# J1.net
KiCad netlist of a schematic drawn in Altium Designer
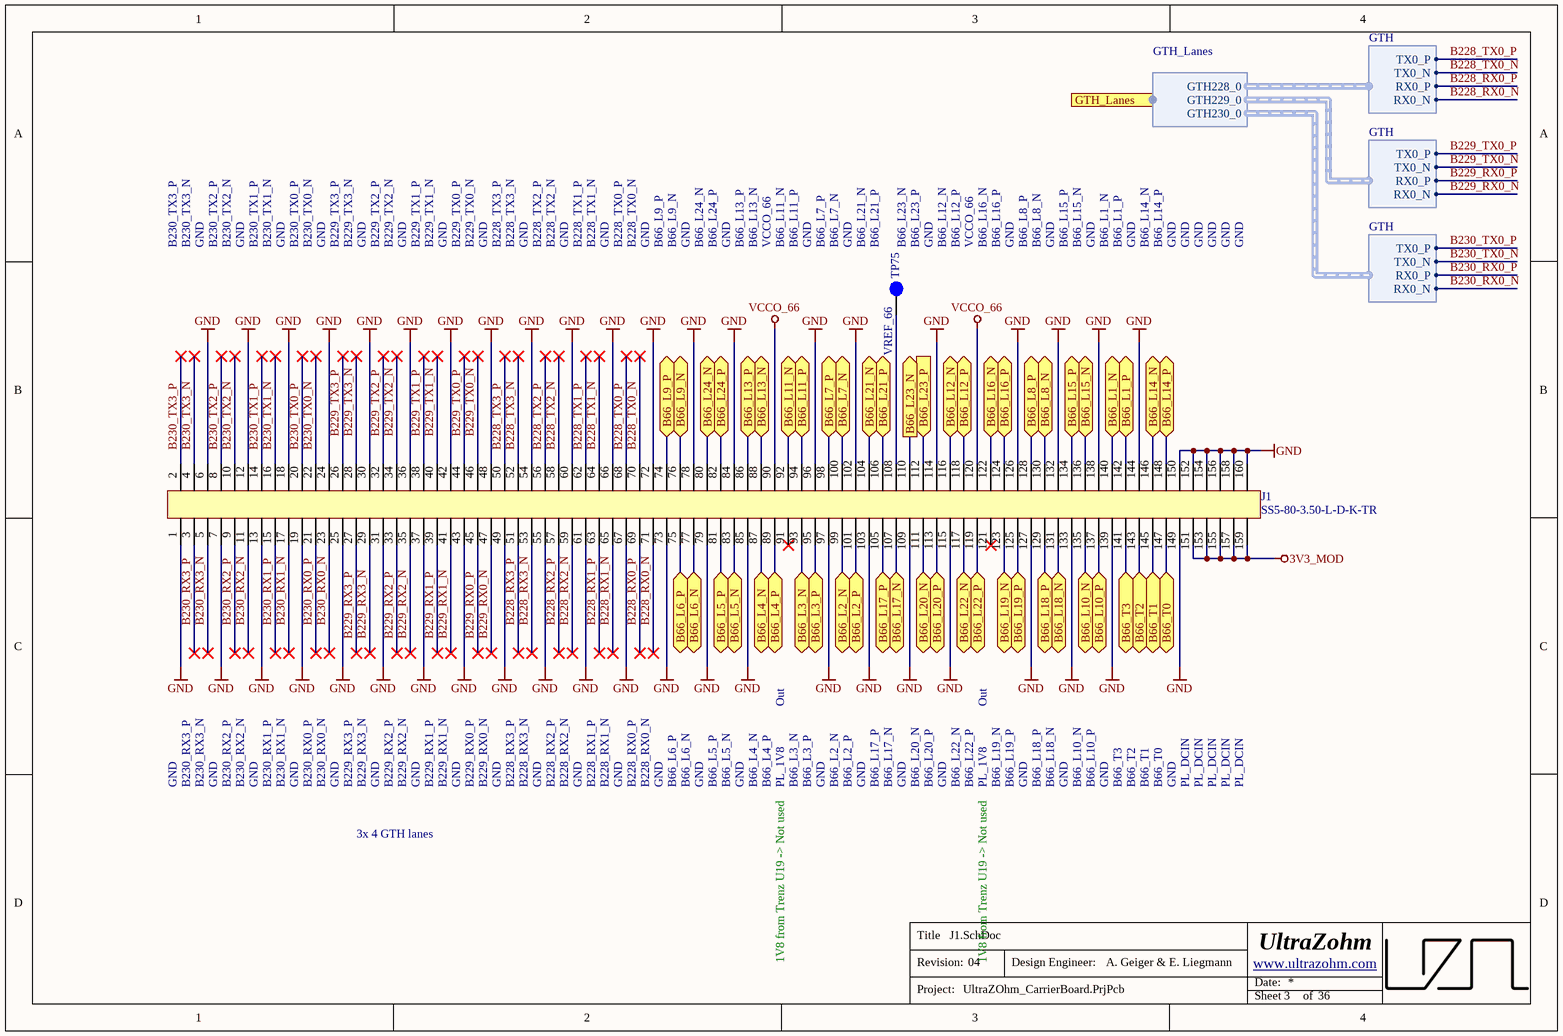
[diagram p0: J1.SchDoc]

(export (version "E")
  (design (tool "Eeschema 10.0.6"))
  (components
    (comp (ref "J1")
      (value "SS5-80-3.50-L-D-K-TR")
      (footprint "SS5-80-3.50-L-D-K-TR")
      (description "0.5 mm Ultra Fine Pitch Socket REF192552-01, 160 Pins")
      (fields
        (field (name "MANUFACTURER") "SAMTEC")
        (field (name "LCSC PART NUMBER") "C5292077")
        (field (name "CREATED FROM") "MGremer")
      )
      (libsource (lib "user") (part "SS5-80-3.50-L-D-K-TR"))
    )
    (comp (ref "TP75") (value "Testpoint 1mm") (footprint "TP_1mm") (libsource (lib "TE") (part "TP")))
  )
  (nets
    (net (code "3") (name "/B66_L1_N") (class "Default")
      (node (ref "J1") (pin "140") (pinfunction "140_140") (pintype "passive"))
    )
    (net (code "4") (name "/B66_L1_P") (class "Default")
      (node (ref "J1") (pin "142") (pinfunction "142_142") (pintype "passive"))
    )
    (net (code "5") (name "/B66_L2_N") (class "Default")
      (node (ref "J1") (pin "99") (pinfunction "99_99") (pintype "passive"))
    )
    (net (code "6") (name "/B66_L2_P") (class "Default")
      (node (ref "J1") (pin "101") (pinfunction "101_101") (pintype "passive"))
    )
    (net (code "7") (name "/B66_L3_N") (class "Default")
      (node (ref "J1") (pin "93") (pinfunction "93_93") (pintype "passive"))
    )
    (net (code "8") (name "/B66_L3_P") (class "Default")
      (node (ref "J1") (pin "95") (pinfunction "95_95") (pintype "passive"))
    )
    (net (code "9") (name "/B66_L4_N") (class "Default")
      (node (ref "J1") (pin "87") (pinfunction "87_87") (pintype "passive"))
    )
    (net (code "10") (name "/B66_L4_P") (class "Default")
      (node (ref "J1") (pin "89") (pinfunction "89_89") (pintype "passive"))
    )
    (net (code "11") (name "/B66_L5_N") (class "Default")
      (node (ref "J1") (pin "83") (pinfunction "83_83") (pintype "passive"))
    )
    (net (code "12") (name "/B66_L5_P") (class "Default")
      (node (ref "J1") (pin "81") (pinfunction "81_81") (pintype "passive"))
    )
    (net (code "13") (name "/B66_L6_N") (class "Default")
      (node (ref "J1") (pin "77") (pinfunction "77_77") (pintype "passive"))
    )
    (net (code "14") (name "/B66_L6_P") (class "Default")
      (node (ref "J1") (pin "75") (pinfunction "75_75") (pintype "passive"))
    )
    (net (code "15") (name "/B66_L7_N") (class "Default")
      (node (ref "J1") (pin "100") (pinfunction "100_100") (pintype "passive"))
    )
    (net (code "16") (name "/B66_L7_P") (class "Default")
      (node (ref "J1") (pin "98") (pinfunction "98_98") (pintype "passive"))
    )
    (net (code "17") (name "/B66_L8_N") (class "Default")
      (node (ref "J1") (pin "130") (pinfunction "130_130") (pintype "passive"))
    )
    (net (code "18") (name "/B66_L8_P") (class "Default")
      (node (ref "J1") (pin "128") (pinfunction "128_128") (pintype "passive"))
    )
    (net (code "19") (name "/B66_L9_N") (class "Default")
      (node (ref "J1") (pin "76") (pinfunction "76_76") (pintype "passive"))
    )
    (net (code "20") (name "/B66_L9_P") (class "Default")
      (node (ref "J1") (pin "74") (pinfunction "74_74") (pintype "passive"))
    )
    (net (code "21") (name "/B66_L10_N") (class "Default")
      (node (ref "J1") (pin "135") (pinfunction "135_135") (pintype "passive"))
    )
    (net (code "22") (name "/B66_L10_P") (class "Default")
      (node (ref "J1") (pin "137") (pinfunction "137_137") (pintype "passive"))
    )
    (net (code "23") (name "/B66_L11_N") (class "Default")
      (node (ref "J1") (pin "92") (pinfunction "92_92") (pintype "passive"))
    )
    (net (code "24") (name "/B66_L11_P") (class "Default")
      (node (ref "J1") (pin "94") (pinfunction "94_94") (pintype "passive"))
    )
    (net (code "25") (name "/B66_L12_N") (class "Default")
      (node (ref "J1") (pin "116") (pinfunction "116_116") (pintype "passive"))
    )
    (net (code "26") (name "/B66_L12_P") (class "Default")
      (node (ref "J1") (pin "118") (pinfunction "118_118") (pintype "passive"))
    )
    (net (code "27") (name "/B66_L13_N") (class "Default")
      (node (ref "J1") (pin "88") (pinfunction "88_88") (pintype "passive"))
    )
    (net (code "28") (name "/B66_L13_P") (class "Default")
      (node (ref "J1") (pin "86") (pinfunction "86_86") (pintype "passive"))
    )
    (net (code "29") (name "/B66_L14_N") (class "Default")
      (node (ref "J1") (pin "146") (pinfunction "146_146") (pintype "passive"))
    )
    (net (code "30") (name "/B66_L14_P") (class "Default")
      (node (ref "J1") (pin "148") (pinfunction "148_148") (pintype "passive"))
    )
    (net (code "31") (name "/B66_L15_N") (class "Default")
      (node (ref "J1") (pin "136") (pinfunction "136_136") (pintype "passive"))
    )
    (net (code "32") (name "/B66_L15_P") (class "Default")
      (node (ref "J1") (pin "134") (pinfunction "134_134") (pintype "passive"))
    )
    (net (code "33") (name "/B66_L16_N") (class "Default")
      (node (ref "J1") (pin "122") (pinfunction "122_122") (pintype "passive"))
    )
    (net (code "34") (name "/B66_L16_P") (class "Default")
      (node (ref "J1") (pin "124") (pinfunction "124_124") (pintype "passive"))
    )
    (net (code "35") (name "/B66_L17_N") (class "Default")
      (node (ref "J1") (pin "107") (pinfunction "107_107") (pintype "passive"))
    )
    (net (code "36") (name "/B66_L17_P") (class "Default")
      (node (ref "J1") (pin "105") (pinfunction "105_105") (pintype "passive"))
    )
    (net (code "37") (name "/B66_L18_N") (class "Default")
      (node (ref "J1") (pin "131") (pinfunction "131_131") (pintype "passive"))
    )
    (net (code "38") (name "/B66_L18_P") (class "Default")
      (node (ref "J1") (pin "129") (pinfunction "129_129") (pintype "passive"))
    )
    (net (code "39") (name "/B66_L19_N") (class "Default")
      (node (ref "J1") (pin "123") (pinfunction "123_123") (pintype "passive"))
    )
    (net (code "40") (name "/B66_L19_P") (class "Default")
      (node (ref "J1") (pin "125") (pinfunction "125_125") (pintype "passive"))
    )
    (net (code "41") (name "/B66_L20_N") (class "Default")
      (node (ref "J1") (pin "111") (pinfunction "111_111") (pintype "passive"))
    )
    (net (code "42") (name "/B66_L20_P") (class "Default")
      (node (ref "J1") (pin "113") (pinfunction "113_113") (pintype "passive"))
    )
    (net (code "43") (name "/B66_L21_N") (class "Default")
      (node (ref "J1") (pin "104") (pinfunction "104_104") (pintype "passive"))
    )
    (net (code "44") (name "/B66_L21_P") (class "Default")
      (node (ref "J1") (pin "106") (pinfunction "106_106") (pintype "passive"))
    )
    (net (code "45") (name "/B66_L22_N") (class "Default")
      (node (ref "J1") (pin "117") (pinfunction "117_117") (pintype "passive"))
    )
    (net (code "46") (name "/B66_L22_P") (class "Default")
      (node (ref "J1") (pin "119") (pinfunction "119_119") (pintype "passive"))
    )
    (net (code "47") (name "/B66_L23_N") (class "Default")
      (node (ref "J1") (pin "110") (pinfunction "110_110") (pintype "passive"))
    )
    (net (code "48") (name "/B66_L23_P") (class "Default")
      (node (ref "J1") (pin "112") (pinfunction "112_112") (pintype "passive"))
    )
    (net (code "49") (name "/B66_L24_N") (class "Default")
      (node (ref "J1") (pin "80") (pinfunction "80_80") (pintype "passive"))
    )
    (net (code "50") (name "/B66_L24_P") (class "Default")
      (node (ref "J1") (pin "82") (pinfunction "82_82") (pintype "passive"))
    )
    (net (code "51") (name "/B66_T0") (class "Default")
      (node (ref "J1") (pin "147") (pinfunction "147_147") (pintype "passive"))
    )
    (net (code "52") (name "/B66_T1") (class "Default")
      (node (ref "J1") (pin "145") (pinfunction "145_145") (pintype "passive"))
    )
    (net (code "53") (name "/B66_T2") (class "Default")
      (node (ref "J1") (pin "143") (pinfunction "143_143") (pintype "passive"))
    )
    (net (code "54") (name "/B66_T3") (class "Default")
      (node (ref "J1") (pin "141") (pinfunction "141_141") (pintype "passive"))
    )
    (net (code "55") (name "/B228_RX0_N") (class "Default")
      (node (ref "J1") (pin "71") (pinfunction "71_71") (pintype "passive+no_connect"))
    )
    (net (code "56") (name "/B228_RX0_P") (class "Default")
      (node (ref "J1") (pin "69") (pinfunction "69_69") (pintype "passive+no_connect"))
    )
    (net (code "57") (name "/B228_RX1_N") (class "Default")
      (node (ref "J1") (pin "65") (pinfunction "65_65") (pintype "passive+no_connect"))
    )
    (net (code "58") (name "/B228_RX1_P") (class "Default")
      (node (ref "J1") (pin "63") (pinfunction "63_63") (pintype "passive+no_connect"))
    )
    (net (code "59") (name "/B228_RX2_N") (class "Default")
      (node (ref "J1") (pin "59") (pinfunction "59_59") (pintype "passive+no_connect"))
    )
    (net (code "60") (name "/B228_RX2_P") (class "Default")
      (node (ref "J1") (pin "57") (pinfunction "57_57") (pintype "passive+no_connect"))
    )
    (net (code "61") (name "/B228_RX3_N") (class "Default")
      (node (ref "J1") (pin "53") (pinfunction "53_53") (pintype "passive+no_connect"))
    )
    (net (code "62") (name "/B228_RX3_P") (class "Default")
      (node (ref "J1") (pin "51") (pinfunction "51_51") (pintype "passive+no_connect"))
    )
    (net (code "63") (name "/B228_TX0_N") (class "Default")
      (node (ref "J1") (pin "70") (pinfunction "70_70") (pintype "passive+no_connect"))
    )
    (net (code "64") (name "/B228_TX0_P") (class "Default")
      (node (ref "J1") (pin "68") (pinfunction "68_68") (pintype "passive+no_connect"))
    )
    (net (code "65") (name "/B228_TX1_N") (class "Default")
      (node (ref "J1") (pin "64") (pinfunction "64_64") (pintype "passive+no_connect"))
    )
    (net (code "66") (name "/B228_TX1_P") (class "Default")
      (node (ref "J1") (pin "62") (pinfunction "62_62") (pintype "passive+no_connect"))
    )
    (net (code "67") (name "/B228_TX2_N") (class "Default")
      (node (ref "J1") (pin "58") (pinfunction "58_58") (pintype "passive+no_connect"))
    )
    (net (code "68") (name "/B228_TX2_P") (class "Default")
      (node (ref "J1") (pin "56") (pinfunction "56_56") (pintype "passive+no_connect"))
    )
    (net (code "69") (name "/B228_TX3_N") (class "Default")
      (node (ref "J1") (pin "52") (pinfunction "52_52") (pintype "passive+no_connect"))
    )
    (net (code "70") (name "/B228_TX3_P") (class "Default")
      (node (ref "J1") (pin "50") (pinfunction "50_50") (pintype "passive+no_connect"))
    )
    (net (code "71") (name "/B229_RX0_N") (class "Default")
      (node (ref "J1") (pin "47") (pinfunction "47_47") (pintype "passive+no_connect"))
    )
    (net (code "72") (name "/B229_RX0_P") (class "Default")
      (node (ref "J1") (pin "45") (pinfunction "45_45") (pintype "passive+no_connect"))
    )
    (net (code "73") (name "/B229_RX1_N") (class "Default")
      (node (ref "J1") (pin "41") (pinfunction "41_41") (pintype "passive+no_connect"))
    )
    (net (code "74") (name "/B229_RX1_P") (class "Default")
      (node (ref "J1") (pin "39") (pinfunction "39_39") (pintype "passive+no_connect"))
    )
    (net (code "75") (name "/B229_RX2_N") (class "Default")
      (node (ref "J1") (pin "35") (pinfunction "35_35") (pintype "passive+no_connect"))
    )
    (net (code "76") (name "/B229_RX2_P") (class "Default")
      (node (ref "J1") (pin "33") (pinfunction "33_33") (pintype "passive+no_connect"))
    )
    (net (code "77") (name "/B229_RX3_N") (class "Default")
      (node (ref "J1") (pin "29") (pinfunction "29_29") (pintype "passive+no_connect"))
    )
    (net (code "78") (name "/B229_RX3_P") (class "Default")
      (node (ref "J1") (pin "27") (pinfunction "27_27") (pintype "passive+no_connect"))
    )
    (net (code "79") (name "/B229_TX0_N") (class "Default")
      (node (ref "J1") (pin "46") (pinfunction "46_46") (pintype "passive+no_connect"))
    )
    (net (code "80") (name "/B229_TX0_P") (class "Default")
      (node (ref "J1") (pin "44") (pinfunction "44_44") (pintype "passive+no_connect"))
    )
    (net (code "81") (name "/B229_TX1_N") (class "Default")
      (node (ref "J1") (pin "40") (pinfunction "40_40") (pintype "passive+no_connect"))
    )
    (net (code "82") (name "/B229_TX1_P") (class "Default")
      (node (ref "J1") (pin "38") (pinfunction "38_38") (pintype "passive+no_connect"))
    )
    (net (code "83") (name "/B229_TX2_N") (class "Default")
      (node (ref "J1") (pin "34") (pinfunction "34_34") (pintype "passive+no_connect"))
    )
    (net (code "84") (name "/B229_TX2_P") (class "Default")
      (node (ref "J1") (pin "32") (pinfunction "32_32") (pintype "passive+no_connect"))
    )
    (net (code "85") (name "/B229_TX3_N") (class "Default")
      (node (ref "J1") (pin "28") (pinfunction "28_28") (pintype "passive+no_connect"))
    )
    (net (code "86") (name "/B229_TX3_P") (class "Default")
      (node (ref "J1") (pin "26") (pinfunction "26_26") (pintype "passive+no_connect"))
    )
    (net (code "87") (name "/B230_RX0_N") (class "Default")
      (node (ref "J1") (pin "23") (pinfunction "23_23") (pintype "passive+no_connect"))
    )
    (net (code "88") (name "/B230_RX0_P") (class "Default")
      (node (ref "J1") (pin "21") (pinfunction "21_21") (pintype "passive+no_connect"))
    )
    (net (code "89") (name "/B230_RX1_N") (class "Default")
      (node (ref "J1") (pin "17") (pinfunction "17_17") (pintype "passive+no_connect"))
    )
    (net (code "90") (name "/B230_RX1_P") (class "Default")
      (node (ref "J1") (pin "15") (pinfunction "15_15") (pintype "passive+no_connect"))
    )
    (net (code "91") (name "/B230_RX2_N") (class "Default")
      (node (ref "J1") (pin "11") (pinfunction "11_11") (pintype "passive+no_connect"))
    )
    (net (code "92") (name "/B230_RX2_P") (class "Default")
      (node (ref "J1") (pin "9") (pinfunction "9_9") (pintype "passive+no_connect"))
    )
    (net (code "93") (name "/B230_RX3_N") (class "Default")
      (node (ref "J1") (pin "5") (pinfunction "5_5") (pintype "passive+no_connect"))
    )
    (net (code "94") (name "/B230_RX3_P") (class "Default")
      (node (ref "J1") (pin "3") (pinfunction "3_3") (pintype "passive+no_connect"))
    )
    (net (code "95") (name "/B230_TX0_N") (class "Default")
      (node (ref "J1") (pin "22") (pinfunction "22_22") (pintype "passive+no_connect"))
    )
    (net (code "96") (name "/B230_TX0_P") (class "Default")
      (node (ref "J1") (pin "20") (pinfunction "20_20") (pintype "passive+no_connect"))
    )
    (net (code "97") (name "/B230_TX1_N") (class "Default")
      (node (ref "J1") (pin "16") (pinfunction "16_16") (pintype "passive+no_connect"))
    )
    (net (code "98") (name "/B230_TX1_P") (class "Default")
      (node (ref "J1") (pin "14") (pinfunction "14_14") (pintype "passive+no_connect"))
    )
    (net (code "99") (name "/B230_TX2_N") (class "Default")
      (node (ref "J1") (pin "10") (pinfunction "10_10") (pintype "passive+no_connect"))
    )
    (net (code "100") (name "/B230_TX2_P") (class "Default")
      (node (ref "J1") (pin "8") (pinfunction "8_8") (pintype "passive+no_connect"))
    )
    (net (code "101") (name "/B230_TX3_N") (class "Default")
      (node (ref "J1") (pin "4") (pinfunction "4_4") (pintype "passive+no_connect"))
    )
    (net (code "102") (name "/B230_TX3_P") (class "Default")
      (node (ref "J1") (pin "2") (pinfunction "2_2") (pintype "passive+no_connect"))
    )
    (net (code "105") (name "3V3_MOD") (class "Default")
      (node (ref "J1") (pin "151") (pinfunction "151_151") (pintype "passive"))
      (node (ref "J1") (pin "153") (pinfunction "153_153") (pintype "passive"))
      (node (ref "J1") (pin "155") (pinfunction "155_155") (pintype "passive"))
      (node (ref "J1") (pin "157") (pinfunction "157_157") (pintype "passive"))
      (node (ref "J1") (pin "159") (pinfunction "159_159") (pintype "passive"))
    )
    (net (code "106") (name "GND") (class "Default")
      (node (ref "J1") (pin "1") (pinfunction "1_1") (pintype "passive"))
      (node (ref "J1") (pin "102") (pinfunction "102_102") (pintype "passive"))
      (node (ref "J1") (pin "103") (pinfunction "103_103") (pintype "passive"))
      (node (ref "J1") (pin "109") (pinfunction "109_109") (pintype "passive"))
      (node (ref "J1") (pin "114") (pinfunction "114_114") (pintype "passive"))
      (node (ref "J1") (pin "115") (pinfunction "115_115") (pintype "passive"))
      (node (ref "J1") (pin "12") (pinfunction "12_12") (pintype "passive"))
      (node (ref "J1") (pin "126") (pinfunction "126_126") (pintype "passive"))
      (node (ref "J1") (pin "127") (pinfunction "127_127") (pintype "passive"))
      (node (ref "J1") (pin "13") (pinfunction "13_13") (pintype "passive"))
      (node (ref "J1") (pin "132") (pinfunction "132_132") (pintype "passive"))
      (node (ref "J1") (pin "133") (pinfunction "133_133") (pintype "passive"))
      (node (ref "J1") (pin "138") (pinfunction "138_138") (pintype "passive"))
      (node (ref "J1") (pin "139") (pinfunction "139_139") (pintype "passive"))
      (node (ref "J1") (pin "144") (pinfunction "144_144") (pintype "passive"))
      (node (ref "J1") (pin "149") (pinfunction "149_149") (pintype "passive"))
      (node (ref "J1") (pin "150") (pinfunction "150_150") (pintype "passive"))
      (node (ref "J1") (pin "152") (pinfunction "152_152") (pintype "passive"))
      (node (ref "J1") (pin "154") (pinfunction "154_154") (pintype "passive"))
      (node (ref "J1") (pin "156") (pinfunction "156_156") (pintype "passive"))
      (node (ref "J1") (pin "158") (pinfunction "158_158") (pintype "passive"))
      (node (ref "J1") (pin "160") (pinfunction "160_160") (pintype "passive"))
      (node (ref "J1") (pin "18") (pinfunction "18_18") (pintype "passive"))
      (node (ref "J1") (pin "19") (pinfunction "19_19") (pintype "passive"))
      (node (ref "J1") (pin "24") (pinfunction "24_24") (pintype "passive"))
      (node (ref "J1") (pin "25") (pinfunction "25_25") (pintype "passive"))
      (node (ref "J1") (pin "30") (pinfunction "30_30") (pintype "passive"))
      (node (ref "J1") (pin "31") (pinfunction "31_31") (pintype "passive"))
      (node (ref "J1") (pin "36") (pinfunction "36_36") (pintype "passive"))
      (node (ref "J1") (pin "37") (pinfunction "37_37") (pintype "passive"))
      (node (ref "J1") (pin "42") (pinfunction "42_42") (pintype "passive"))
      (node (ref "J1") (pin "43") (pinfunction "43_43") (pintype "passive"))
      (node (ref "J1") (pin "48") (pinfunction "48_48") (pintype "passive"))
      (node (ref "J1") (pin "49") (pinfunction "49_49") (pintype "passive"))
      (node (ref "J1") (pin "54") (pinfunction "54_54") (pintype "passive"))
      (node (ref "J1") (pin "55") (pinfunction "55_55") (pintype "passive"))
      (node (ref "J1") (pin "6") (pinfunction "6_6") (pintype "passive"))
      (node (ref "J1") (pin "60") (pinfunction "60_60") (pintype "passive"))
      (node (ref "J1") (pin "61") (pinfunction "61_61") (pintype "passive"))
      (node (ref "J1") (pin "66") (pinfunction "66_66") (pintype "passive"))
      (node (ref "J1") (pin "67") (pinfunction "67_67") (pintype "passive"))
      (node (ref "J1") (pin "7") (pinfunction "7_7") (pintype "passive"))
      (node (ref "J1") (pin "72") (pinfunction "72_72") (pintype "passive"))
      (node (ref "J1") (pin "73") (pinfunction "73_73") (pintype "passive"))
      (node (ref "J1") (pin "78") (pinfunction "78_78") (pintype "passive"))
      (node (ref "J1") (pin "79") (pinfunction "79_79") (pintype "passive"))
      (node (ref "J1") (pin "84") (pinfunction "84_84") (pintype "passive"))
      (node (ref "J1") (pin "85") (pinfunction "85_85") (pintype "passive"))
      (node (ref "J1") (pin "96") (pinfunction "96_96") (pintype "passive"))
      (node (ref "J1") (pin "97") (pinfunction "97_97") (pintype "passive"))
    )
    (net (code "107") (name "Net-(J1-Pad108)") (class "Default")
      (node (ref "J1") (pin "108") (pinfunction "108_108") (pintype "passive"))
      (node (ref "TP75") (pin "1") (pintype "passive"))
    )
    (net (code "108") (name "VCCO_66") (class "Default")
      (node (ref "J1") (pin "120") (pinfunction "120_120") (pintype "passive"))
      (node (ref "J1") (pin "90") (pinfunction "90_90") (pintype "passive"))
    )
    (net (code "109") (name "unconnected-(J1-Pad91)") (class "Default")
      (node (ref "J1") (pin "91") (pinfunction "91_91") (pintype "passive+no_connect"))
    )
    (net (code "110") (name "unconnected-(J1-Pad121)") (class "Default")
      (node (ref "J1") (pin "121") (pinfunction "121_121") (pintype "passive+no_connect"))
    )
  )
)
